# schematic.net
KiCad netlist of a schematic drawn in EasyEDA
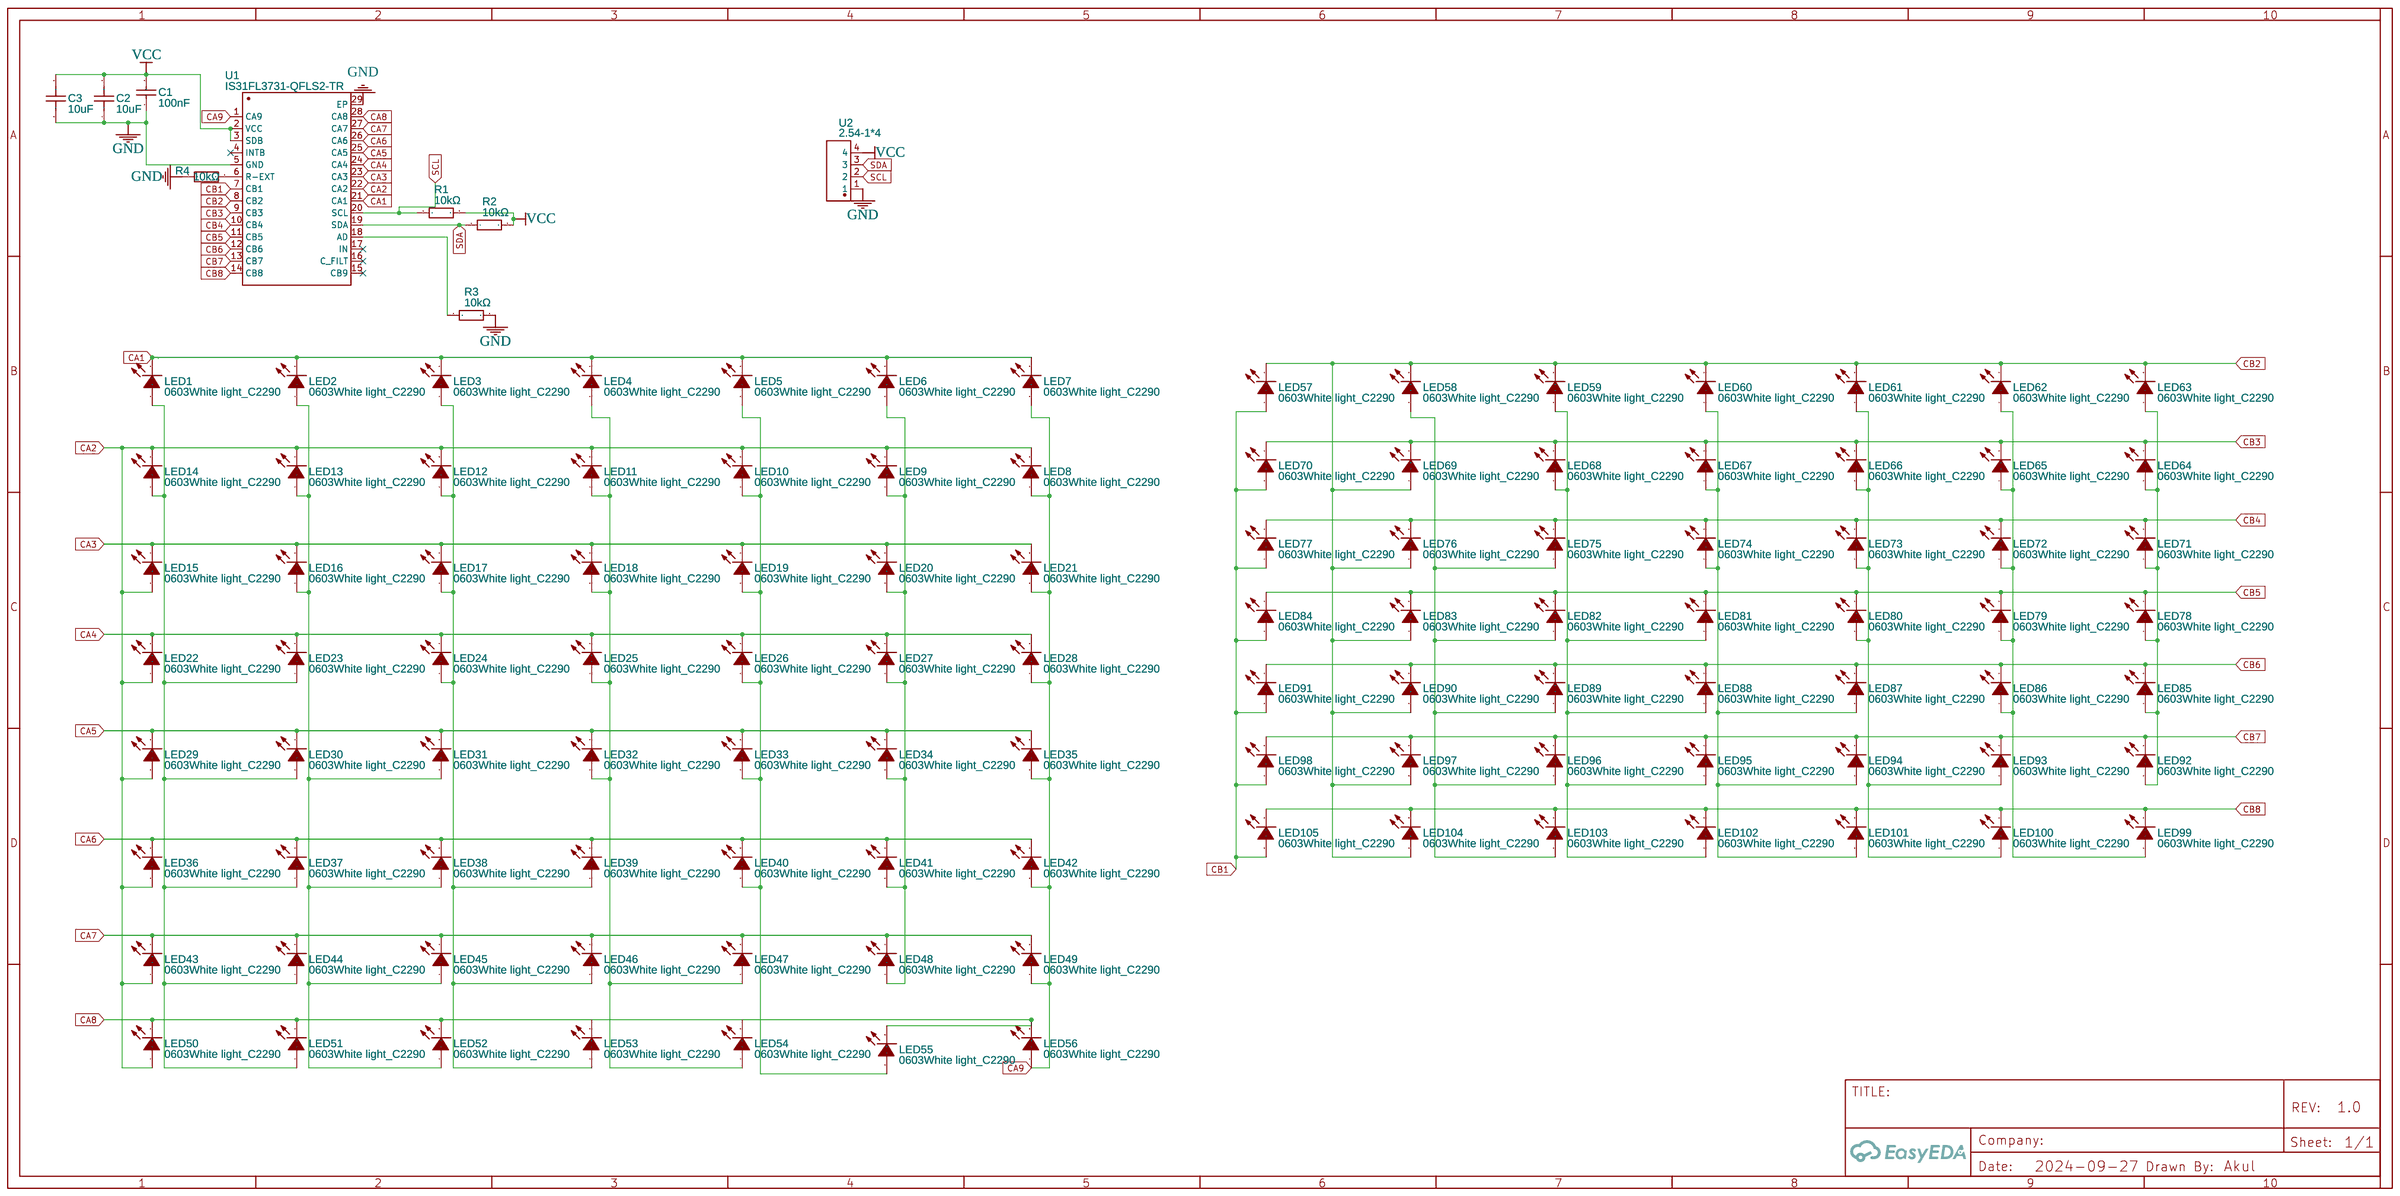
[diagram p0: schematic sheet]

(export (version "E")
  (design (tool "Eeschema 10.0.6"))
  (components
    (comp (ref "C1")
      (value "100nF")
      (fields
        (field (name "Manufacturer Part") "CL05B104KO5NNNC")
        (field (name "Manufacturer") "SAMSUNG(三星)")
      )
      (libsource (lib "") (part "CL05B104KO5NNNC"))
    )
    (comp (ref "C2")
      (value "10uF")
      (fields
        (field (name "Manufacturer Part") "CL10A106KP8NNNC")
        (field (name "Manufacturer") "SAMSUNG(三星)")
      )
      (libsource (lib "") (part "CL10A106KP8NNNC"))
    )
    (comp (ref "C3")
      (value "10uF")
      (fields
        (field (name "Manufacturer Part") "CL10A106KP8NNNC")
        (field (name "Manufacturer") "SAMSUNG(三星)")
      )
      (libsource (lib "") (part "CL10A106KP8NNNC"))
    )
    (comp (ref "LED1")
      (value "0603White light_C2290")
      (fields (field (name "Manufacturer Part") "KT-0603白灯") (field (name "Manufacturer") "KENTO"))
      (libsource (lib "") (part "0603White light_C2290"))
    )
    (comp (ref "LED2")
      (value "0603White light_C2290")
      (fields (field (name "Manufacturer Part") "KT-0603白灯") (field (name "Manufacturer") "KENTO"))
      (libsource (lib "") (part "0603White light_C2290"))
    )
    (comp (ref "LED3")
      (value "0603White light_C2290")
      (fields (field (name "Manufacturer Part") "KT-0603白灯") (field (name "Manufacturer") "KENTO"))
      (libsource (lib "") (part "0603White light_C2290"))
    )
    (comp (ref "LED4")
      (value "0603White light_C2290")
      (fields (field (name "Manufacturer Part") "KT-0603白灯") (field (name "Manufacturer") "KENTO"))
      (libsource (lib "") (part "0603White light_C2290"))
    )
    (comp (ref "LED5")
      (value "0603White light_C2290")
      (fields (field (name "Manufacturer Part") "KT-0603白灯") (field (name "Manufacturer") "KENTO"))
      (libsource (lib "") (part "0603White light_C2290"))
    )
    (comp (ref "LED6")
      (value "0603White light_C2290")
      (fields (field (name "Manufacturer Part") "KT-0603白灯") (field (name "Manufacturer") "KENTO"))
      (libsource (lib "") (part "0603White light_C2290"))
    )
    (comp (ref "LED7")
      (value "0603White light_C2290")
      (fields (field (name "Manufacturer Part") "KT-0603白灯") (field (name "Manufacturer") "KENTO"))
      (libsource (lib "") (part "0603White light_C2290"))
    )
    (comp (ref "LED8")
      (value "0603White light_C2290")
      (fields (field (name "Manufacturer Part") "KT-0603白灯") (field (name "Manufacturer") "KENTO"))
      (libsource (lib "") (part "0603White light_C2290"))
    )
    (comp (ref "LED9")
      (value "0603White light_C2290")
      (fields (field (name "Manufacturer Part") "KT-0603白灯") (field (name "Manufacturer") "KENTO"))
      (libsource (lib "") (part "0603White light_C2290"))
    )
    (comp (ref "LED10")
      (value "0603White light_C2290")
      (fields (field (name "Manufacturer Part") "KT-0603白灯") (field (name "Manufacturer") "KENTO"))
      (libsource (lib "") (part "0603White light_C2290"))
    )
    (comp (ref "LED11")
      (value "0603White light_C2290")
      (fields (field (name "Manufacturer Part") "KT-0603白灯") (field (name "Manufacturer") "KENTO"))
      (libsource (lib "") (part "0603White light_C2290"))
    )
    (comp (ref "LED12")
      (value "0603White light_C2290")
      (fields (field (name "Manufacturer Part") "KT-0603白灯") (field (name "Manufacturer") "KENTO"))
      (libsource (lib "") (part "0603White light_C2290"))
    )
    (comp (ref "LED13")
      (value "0603White light_C2290")
      (fields (field (name "Manufacturer Part") "KT-0603白灯") (field (name "Manufacturer") "KENTO"))
      (libsource (lib "") (part "0603White light_C2290"))
    )
    (comp (ref "LED14")
      (value "0603White light_C2290")
      (fields (field (name "Manufacturer Part") "KT-0603白灯") (field (name "Manufacturer") "KENTO"))
      (libsource (lib "") (part "0603White light_C2290"))
    )
    (comp (ref "LED15")
      (value "0603White light_C2290")
      (fields (field (name "Manufacturer Part") "KT-0603白灯") (field (name "Manufacturer") "KENTO"))
      (libsource (lib "") (part "0603White light_C2290"))
    )
    (comp (ref "LED16")
      (value "0603White light_C2290")
      (fields (field (name "Manufacturer Part") "KT-0603白灯") (field (name "Manufacturer") "KENTO"))
      (libsource (lib "") (part "0603White light_C2290"))
    )
    (comp (ref "LED17")
      (value "0603White light_C2290")
      (fields (field (name "Manufacturer Part") "KT-0603白灯") (field (name "Manufacturer") "KENTO"))
      (libsource (lib "") (part "0603White light_C2290"))
    )
    (comp (ref "LED18")
      (value "0603White light_C2290")
      (fields (field (name "Manufacturer Part") "KT-0603白灯") (field (name "Manufacturer") "KENTO"))
      (libsource (lib "") (part "0603White light_C2290"))
    )
    (comp (ref "LED19")
      (value "0603White light_C2290")
      (fields (field (name "Manufacturer Part") "KT-0603白灯") (field (name "Manufacturer") "KENTO"))
      (libsource (lib "") (part "0603White light_C2290"))
    )
    (comp (ref "LED20")
      (value "0603White light_C2290")
      (fields (field (name "Manufacturer Part") "KT-0603白灯") (field (name "Manufacturer") "KENTO"))
      (libsource (lib "") (part "0603White light_C2290"))
    )
    (comp (ref "LED21")
      (value "0603White light_C2290")
      (fields (field (name "Manufacturer Part") "KT-0603白灯") (field (name "Manufacturer") "KENTO"))
      (libsource (lib "") (part "0603White light_C2290"))
    )
    (comp (ref "LED22")
      (value "0603White light_C2290")
      (fields (field (name "Manufacturer Part") "KT-0603白灯") (field (name "Manufacturer") "KENTO"))
      (libsource (lib "") (part "0603White light_C2290"))
    )
    (comp (ref "LED23")
      (value "0603White light_C2290")
      (fields (field (name "Manufacturer Part") "KT-0603白灯") (field (name "Manufacturer") "KENTO"))
      (libsource (lib "") (part "0603White light_C2290"))
    )
    (comp (ref "LED24")
      (value "0603White light_C2290")
      (fields (field (name "Manufacturer Part") "KT-0603白灯") (field (name "Manufacturer") "KENTO"))
      (libsource (lib "") (part "0603White light_C2290"))
    )
    (comp (ref "LED25")
      (value "0603White light_C2290")
      (fields (field (name "Manufacturer Part") "KT-0603白灯") (field (name "Manufacturer") "KENTO"))
      (libsource (lib "") (part "0603White light_C2290"))
    )
    (comp (ref "LED26")
      (value "0603White light_C2290")
      (fields (field (name "Manufacturer Part") "KT-0603白灯") (field (name "Manufacturer") "KENTO"))
      (libsource (lib "") (part "0603White light_C2290"))
    )
    (comp (ref "LED27")
      (value "0603White light_C2290")
      (fields (field (name "Manufacturer Part") "KT-0603白灯") (field (name "Manufacturer") "KENTO"))
      (libsource (lib "") (part "0603White light_C2290"))
    )
    (comp (ref "LED28")
      (value "0603White light_C2290")
      (fields (field (name "Manufacturer Part") "KT-0603白灯") (field (name "Manufacturer") "KENTO"))
      (libsource (lib "") (part "0603White light_C2290"))
    )
    (comp (ref "LED29")
      (value "0603White light_C2290")
      (fields (field (name "Manufacturer Part") "KT-0603白灯") (field (name "Manufacturer") "KENTO"))
      (libsource (lib "") (part "0603White light_C2290"))
    )
    (comp (ref "LED30")
      (value "0603White light_C2290")
      (fields (field (name "Manufacturer Part") "KT-0603白灯") (field (name "Manufacturer") "KENTO"))
      (libsource (lib "") (part "0603White light_C2290"))
    )
    (comp (ref "LED31")
      (value "0603White light_C2290")
      (fields (field (name "Manufacturer Part") "KT-0603白灯") (field (name "Manufacturer") "KENTO"))
      (libsource (lib "") (part "0603White light_C2290"))
    )
    (comp (ref "LED32")
      (value "0603White light_C2290")
      (fields (field (name "Manufacturer Part") "KT-0603白灯") (field (name "Manufacturer") "KENTO"))
      (libsource (lib "") (part "0603White light_C2290"))
    )
    (comp (ref "LED33")
      (value "0603White light_C2290")
      (fields (field (name "Manufacturer Part") "KT-0603白灯") (field (name "Manufacturer") "KENTO"))
      (libsource (lib "") (part "0603White light_C2290"))
    )
    (comp (ref "LED34")
      (value "0603White light_C2290")
      (fields (field (name "Manufacturer Part") "KT-0603白灯") (field (name "Manufacturer") "KENTO"))
      (libsource (lib "") (part "0603White light_C2290"))
    )
    (comp (ref "LED35")
      (value "0603White light_C2290")
      (fields (field (name "Manufacturer Part") "KT-0603白灯") (field (name "Manufacturer") "KENTO"))
      (libsource (lib "") (part "0603White light_C2290"))
    )
    (comp (ref "LED36")
      (value "0603White light_C2290")
      (fields (field (name "Manufacturer Part") "KT-0603白灯") (field (name "Manufacturer") "KENTO"))
      (libsource (lib "") (part "0603White light_C2290"))
    )
    (comp (ref "LED37")
      (value "0603White light_C2290")
      (fields (field (name "Manufacturer Part") "KT-0603白灯") (field (name "Manufacturer") "KENTO"))
      (libsource (lib "") (part "0603White light_C2290"))
    )
    (comp (ref "LED38")
      (value "0603White light_C2290")
      (fields (field (name "Manufacturer Part") "KT-0603白灯") (field (name "Manufacturer") "KENTO"))
      (libsource (lib "") (part "0603White light_C2290"))
    )
    (comp (ref "LED39")
      (value "0603White light_C2290")
      (fields (field (name "Manufacturer Part") "KT-0603白灯") (field (name "Manufacturer") "KENTO"))
      (libsource (lib "") (part "0603White light_C2290"))
    )
    (comp (ref "LED40")
      (value "0603White light_C2290")
      (fields (field (name "Manufacturer Part") "KT-0603白灯") (field (name "Manufacturer") "KENTO"))
      (libsource (lib "") (part "0603White light_C2290"))
    )
    (comp (ref "LED41")
      (value "0603White light_C2290")
      (fields (field (name "Manufacturer Part") "KT-0603白灯") (field (name "Manufacturer") "KENTO"))
      (libsource (lib "") (part "0603White light_C2290"))
    )
    (comp (ref "LED42")
      (value "0603White light_C2290")
      (fields (field (name "Manufacturer Part") "KT-0603白灯") (field (name "Manufacturer") "KENTO"))
      (libsource (lib "") (part "0603White light_C2290"))
    )
    (comp (ref "LED43")
      (value "0603White light_C2290")
      (fields (field (name "Manufacturer Part") "KT-0603白灯") (field (name "Manufacturer") "KENTO"))
      (libsource (lib "") (part "0603White light_C2290"))
    )
    (comp (ref "LED44")
      (value "0603White light_C2290")
      (fields (field (name "Manufacturer Part") "KT-0603白灯") (field (name "Manufacturer") "KENTO"))
      (libsource (lib "") (part "0603White light_C2290"))
    )
    (comp (ref "LED45")
      (value "0603White light_C2290")
      (fields (field (name "Manufacturer Part") "KT-0603白灯") (field (name "Manufacturer") "KENTO"))
      (libsource (lib "") (part "0603White light_C2290"))
    )
    (comp (ref "LED46")
      (value "0603White light_C2290")
      (fields (field (name "Manufacturer Part") "KT-0603白灯") (field (name "Manufacturer") "KENTO"))
      (libsource (lib "") (part "0603White light_C2290"))
    )
    (comp (ref "LED47")
      (value "0603White light_C2290")
      (fields (field (name "Manufacturer Part") "KT-0603白灯") (field (name "Manufacturer") "KENTO"))
      (libsource (lib "") (part "0603White light_C2290"))
    )
    (comp (ref "LED48")
      (value "0603White light_C2290")
      (fields (field (name "Manufacturer Part") "KT-0603白灯") (field (name "Manufacturer") "KENTO"))
      (libsource (lib "") (part "0603White light_C2290"))
    )
    (comp (ref "LED49")
      (value "0603White light_C2290")
      (fields (field (name "Manufacturer Part") "KT-0603白灯") (field (name "Manufacturer") "KENTO"))
      (libsource (lib "") (part "0603White light_C2290"))
    )
    (comp (ref "LED50")
      (value "0603White light_C2290")
      (fields (field (name "Manufacturer Part") "KT-0603白灯") (field (name "Manufacturer") "KENTO"))
      (libsource (lib "") (part "0603White light_C2290"))
    )
    (comp (ref "LED51")
      (value "0603White light_C2290")
      (fields (field (name "Manufacturer Part") "KT-0603白灯") (field (name "Manufacturer") "KENTO"))
      (libsource (lib "") (part "0603White light_C2290"))
    )
    (comp (ref "LED52")
      (value "0603White light_C2290")
      (fields (field (name "Manufacturer Part") "KT-0603白灯") (field (name "Manufacturer") "KENTO"))
      (libsource (lib "") (part "0603White light_C2290"))
    )
    (comp (ref "LED53")
      (value "0603White light_C2290")
      (fields (field (name "Manufacturer Part") "KT-0603白灯") (field (name "Manufacturer") "KENTO"))
      (libsource (lib "") (part "0603White light_C2290"))
    )
    (comp (ref "LED54")
      (value "0603White light_C2290")
      (fields (field (name "Manufacturer Part") "KT-0603白灯") (field (name "Manufacturer") "KENTO"))
      (libsource (lib "") (part "0603White light_C2290"))
    )
    (comp (ref "LED55")
      (value "0603White light_C2290")
      (fields (field (name "Manufacturer Part") "KT-0603白灯") (field (name "Manufacturer") "KENTO"))
      (libsource (lib "") (part "0603White light_C2290"))
    )
    (comp (ref "LED56")
      (value "0603White light_C2290")
      (fields (field (name "Manufacturer Part") "KT-0603白灯") (field (name "Manufacturer") "KENTO"))
      (libsource (lib "") (part "0603White light_C2290"))
    )
    (comp (ref "LED57")
      (value "0603White light_C2290")
      (fields (field (name "Manufacturer Part") "KT-0603白灯") (field (name "Manufacturer") "KENTO"))
      (libsource (lib "") (part "0603White light_C2290_1"))
    )
    (comp (ref "LED58")
      (value "0603White light_C2290")
      (fields (field (name "Manufacturer Part") "KT-0603白灯") (field (name "Manufacturer") "KENTO"))
      (libsource (lib "") (part "0603White light_C2290_1"))
    )
    (comp (ref "LED59")
      (value "0603White light_C2290")
      (fields (field (name "Manufacturer Part") "KT-0603白灯") (field (name "Manufacturer") "KENTO"))
      (libsource (lib "") (part "0603White light_C2290_1"))
    )
    (comp (ref "LED60")
      (value "0603White light_C2290")
      (fields (field (name "Manufacturer Part") "KT-0603白灯") (field (name "Manufacturer") "KENTO"))
      (libsource (lib "") (part "0603White light_C2290_1"))
    )
    (comp (ref "LED61")
      (value "0603White light_C2290")
      (fields (field (name "Manufacturer Part") "KT-0603白灯") (field (name "Manufacturer") "KENTO"))
      (libsource (lib "") (part "0603White light_C2290_1"))
    )
    (comp (ref "LED62")
      (value "0603White light_C2290")
      (fields (field (name "Manufacturer Part") "KT-0603白灯") (field (name "Manufacturer") "KENTO"))
      (libsource (lib "") (part "0603White light_C2290_1"))
    )
    (comp (ref "LED63")
      (value "0603White light_C2290")
      (fields (field (name "Manufacturer Part") "KT-0603白灯") (field (name "Manufacturer") "KENTO"))
      (libsource (lib "") (part "0603White light_C2290_1"))
    )
    (comp (ref "LED64")
      (value "0603White light_C2290")
      (fields (field (name "Manufacturer Part") "KT-0603白灯") (field (name "Manufacturer") "KENTO"))
      (libsource (lib "") (part "0603White light_C2290_1"))
    )
    (comp (ref "LED65")
      (value "0603White light_C2290")
      (fields (field (name "Manufacturer Part") "KT-0603白灯") (field (name "Manufacturer") "KENTO"))
      (libsource (lib "") (part "0603White light_C2290_1"))
    )
    (comp (ref "LED66")
      (value "0603White light_C2290")
      (fields (field (name "Manufacturer Part") "KT-0603白灯") (field (name "Manufacturer") "KENTO"))
      (libsource (lib "") (part "0603White light_C2290_1"))
    )
    (comp (ref "LED67")
      (value "0603White light_C2290")
      (fields (field (name "Manufacturer Part") "KT-0603白灯") (field (name "Manufacturer") "KENTO"))
      (libsource (lib "") (part "0603White light_C2290_1"))
    )
    (comp (ref "LED68")
      (value "0603White light_C2290")
      (fields (field (name "Manufacturer Part") "KT-0603白灯") (field (name "Manufacturer") "KENTO"))
      (libsource (lib "") (part "0603White light_C2290_1"))
    )
    (comp (ref "LED69")
      (value "0603White light_C2290")
      (fields (field (name "Manufacturer Part") "KT-0603白灯") (field (name "Manufacturer") "KENTO"))
      (libsource (lib "") (part "0603White light_C2290_1"))
    )
    (comp (ref "LED70")
      (value "0603White light_C2290")
      (fields (field (name "Manufacturer Part") "KT-0603白灯") (field (name "Manufacturer") "KENTO"))
      (libsource (lib "") (part "0603White light_C2290_1"))
    )
    (comp (ref "LED71")
      (value "0603White light_C2290")
      (fields (field (name "Manufacturer Part") "KT-0603白灯") (field (name "Manufacturer") "KENTO"))
      (libsource (lib "") (part "0603White light_C2290_1"))
    )
    (comp (ref "LED72")
      (value "0603White light_C2290")
      (fields (field (name "Manufacturer Part") "KT-0603白灯") (field (name "Manufacturer") "KENTO"))
      (libsource (lib "") (part "0603White light_C2290_1"))
    )
    (comp (ref "LED73")
      (value "0603White light_C2290")
      (fields (field (name "Manufacturer Part") "KT-0603白灯") (field (name "Manufacturer") "KENTO"))
      (libsource (lib "") (part "0603White light_C2290_1"))
    )
    (comp (ref "LED74")
      (value "0603White light_C2290")
      (fields (field (name "Manufacturer Part") "KT-0603白灯") (field (name "Manufacturer") "KENTO"))
      (libsource (lib "") (part "0603White light_C2290_1"))
    )
    (comp (ref "LED75")
      (value "0603White light_C2290")
      (fields (field (name "Manufacturer Part") "KT-0603白灯") (field (name "Manufacturer") "KENTO"))
      (libsource (lib "") (part "0603White light_C2290_1"))
    )
    (comp (ref "LED76")
      (value "0603White light_C2290")
      (fields (field (name "Manufacturer Part") "KT-0603白灯") (field (name "Manufacturer") "KENTO"))
      (libsource (lib "") (part "0603White light_C2290_1"))
    )
    (comp (ref "LED77")
      (value "0603White light_C2290")
      (fields (field (name "Manufacturer Part") "KT-0603白灯") (field (name "Manufacturer") "KENTO"))
      (libsource (lib "") (part "0603White light_C2290_1"))
    )
    (comp (ref "LED78")
      (value "0603White light_C2290")
      (fields (field (name "Manufacturer Part") "KT-0603白灯") (field (name "Manufacturer") "KENTO"))
      (libsource (lib "") (part "0603White light_C2290_1"))
    )
    (comp (ref "LED79")
      (value "0603White light_C2290")
      (fields (field (name "Manufacturer Part") "KT-0603白灯") (field (name "Manufacturer") "KENTO"))
      (libsource (lib "") (part "0603White light_C2290_1"))
    )
    (comp (ref "LED80")
      (value "0603White light_C2290")
      (fields (field (name "Manufacturer Part") "KT-0603白灯") (field (name "Manufacturer") "KENTO"))
      (libsource (lib "") (part "0603White light_C2290_1"))
    )
    (comp (ref "LED81")
      (value "0603White light_C2290")
      (fields (field (name "Manufacturer Part") "KT-0603白灯") (field (name "Manufacturer") "KENTO"))
      (libsource (lib "") (part "0603White light_C2290_1"))
    )
    (comp (ref "LED82")
      (value "0603White light_C2290")
      (fields (field (name "Manufacturer Part") "KT-0603白灯") (field (name "Manufacturer") "KENTO"))
      (libsource (lib "") (part "0603White light_C2290_1"))
    )
    (comp (ref "LED83")
      (value "0603White light_C2290")
      (fields (field (name "Manufacturer Part") "KT-0603白灯") (field (name "Manufacturer") "KENTO"))
      (libsource (lib "") (part "0603White light_C2290_1"))
    )
    (comp (ref "LED84")
      (value "0603White light_C2290")
      (fields (field (name "Manufacturer Part") "KT-0603白灯") (field (name "Manufacturer") "KENTO"))
      (libsource (lib "") (part "0603White light_C2290_1"))
    )
    (comp (ref "LED85")
      (value "0603White light_C2290")
      (fields (field (name "Manufacturer Part") "KT-0603白灯") (field (name "Manufacturer") "KENTO"))
      (libsource (lib "") (part "0603White light_C2290_1"))
    )
    (comp (ref "LED86")
      (value "0603White light_C2290")
      (fields (field (name "Manufacturer Part") "KT-0603白灯") (field (name "Manufacturer") "KENTO"))
      (libsource (lib "") (part "0603White light_C2290_1"))
    )
    (comp (ref "LED87")
      (value "0603White light_C2290")
      (fields (field (name "Manufacturer Part") "KT-0603白灯") (field (name "Manufacturer") "KENTO"))
      (libsource (lib "") (part "0603White light_C2290_1"))
    )
    (comp (ref "LED88")
      (value "0603White light_C2290")
      (fields (field (name "Manufacturer Part") "KT-0603白灯") (field (name "Manufacturer") "KENTO"))
      (libsource (lib "") (part "0603White light_C2290_1"))
    )
    (comp (ref "LED89")
      (value "0603White light_C2290")
      (fields (field (name "Manufacturer Part") "KT-0603白灯") (field (name "Manufacturer") "KENTO"))
      (libsource (lib "") (part "0603White light_C2290_1"))
    )
    (comp (ref "LED90")
      (value "0603White light_C2290")
      (fields (field (name "Manufacturer Part") "KT-0603白灯") (field (name "Manufacturer") "KENTO"))
      (libsource (lib "") (part "0603White light_C2290_1"))
    )
    (comp (ref "LED91")
      (value "0603White light_C2290")
      (fields (field (name "Manufacturer Part") "KT-0603白灯") (field (name "Manufacturer") "KENTO"))
      (libsource (lib "") (part "0603White light_C2290_1"))
    )
    (comp (ref "LED92")
      (value "0603White light_C2290")
      (fields (field (name "Manufacturer Part") "KT-0603白灯") (field (name "Manufacturer") "KENTO"))
      (libsource (lib "") (part "0603White light_C2290_1"))
    )
    (comp (ref "LED93")
      (value "0603White light_C2290")
      (fields (field (name "Manufacturer Part") "KT-0603白灯") (field (name "Manufacturer") "KENTO"))
      (libsource (lib "") (part "0603White light_C2290_1"))
    )
    (comp (ref "LED94")
      (value "0603White light_C2290")
      (fields (field (name "Manufacturer Part") "KT-0603白灯") (field (name "Manufacturer") "KENTO"))
      (libsource (lib "") (part "0603White light_C2290_1"))
    )
    (comp (ref "LED95")
      (value "0603White light_C2290")
      (fields (field (name "Manufacturer Part") "KT-0603白灯") (field (name "Manufacturer") "KENTO"))
      (libsource (lib "") (part "0603White light_C2290_1"))
    )
    (comp (ref "LED96")
      (value "0603White light_C2290")
      (fields (field (name "Manufacturer Part") "KT-0603白灯") (field (name "Manufacturer") "KENTO"))
      (libsource (lib "") (part "0603White light_C2290_1"))
    )
    (comp (ref "LED97")
      (value "0603White light_C2290")
      (fields (field (name "Manufacturer Part") "KT-0603白灯") (field (name "Manufacturer") "KENTO"))
      (libsource (lib "") (part "0603White light_C2290_1"))
    )
    (comp (ref "LED98")
      (value "0603White light_C2290")
      (fields (field (name "Manufacturer Part") "KT-0603白灯") (field (name "Manufacturer") "KENTO"))
      (libsource (lib "") (part "0603White light_C2290_1"))
    )
    (comp (ref "LED99")
      (value "0603White light_C2290")
      (fields (field (name "Manufacturer Part") "KT-0603白灯") (field (name "Manufacturer") "KENTO"))
      (libsource (lib "") (part "0603White light_C2290_1"))
    )
    (comp (ref "LED100")
      (value "0603White light_C2290")
      (fields (field (name "Manufacturer Part") "KT-0603白灯") (field (name "Manufacturer") "KENTO"))
      (libsource (lib "") (part "0603White light_C2290_1"))
    )
    (comp (ref "LED101")
      (value "0603White light_C2290")
      (fields (field (name "Manufacturer Part") "KT-0603白灯") (field (name "Manufacturer") "KENTO"))
      (libsource (lib "") (part "0603White light_C2290_1"))
    )
    (comp (ref "LED102")
      (value "0603White light_C2290")
      (fields (field (name "Manufacturer Part") "KT-0603白灯") (field (name "Manufacturer") "KENTO"))
      (libsource (lib "") (part "0603White light_C2290_1"))
    )
    (comp (ref "LED103")
      (value "0603White light_C2290")
      (fields (field (name "Manufacturer Part") "KT-0603白灯") (field (name "Manufacturer") "KENTO"))
      (libsource (lib "") (part "0603White light_C2290_1"))
    )
    (comp (ref "LED104")
      (value "0603White light_C2290")
      (fields (field (name "Manufacturer Part") "KT-0603白灯") (field (name "Manufacturer") "KENTO"))
      (libsource (lib "") (part "0603White light_C2290_1"))
    )
    (comp (ref "LED105")
      (value "0603White light_C2290")
      (fields (field (name "Manufacturer Part") "KT-0603白灯") (field (name "Manufacturer") "KENTO"))
      (libsource (lib "") (part "0603White light_C2290_1"))
    )
    (comp (ref "R1")
      (value "10kΩ")
      (fields
        (field (name "Manufacturer Part") "0402WGF1002TCE")
        (field (name "Manufacturer") "UNI-ROYAL(厚声)")
      )
      (libsource (lib "") (part "0402WGF1002TCE"))
    )
    (comp (ref "R2")
      (value "10kΩ")
      (fields
        (field (name "Manufacturer Part") "0402WGF1002TCE")
        (field (name "Manufacturer") "UNI-ROYAL(厚声)")
      )
      (libsource (lib "") (part "0402WGF1002TCE"))
    )
    (comp (ref "R3")
      (value "10kΩ")
      (fields
        (field (name "Manufacturer Part") "0402WGF1002TCE")
        (field (name "Manufacturer") "UNI-ROYAL(厚声)")
      )
      (libsource (lib "") (part "0402WGF1002TCE"))
    )
    (comp (ref "R4")
      (value "10kΩ")
      (fields
        (field (name "Manufacturer Part") "0402WGF1002TCE")
        (field (name "Manufacturer") "UNI-ROYAL(厚声)")
      )
      (libsource (lib "") (part "0402WGF1002TCE"))
    )
    (comp (ref "U1")
      (value "IS31FL3731-QFLS2-TR")
      (fields (field (name "Manufacturer") "ISSI(美国芯成)"))
      (libsource (lib "") (part "IS31FL3731-QFLS2-TR"))
    )
    (comp (ref "U2")
      (value "2.54-1*4")
      (fields (field (name "Manufacturer") "ZHOURI(洲日)"))
      (libsource (lib "") (part "2.54-1*4"))
    )
  )
  (nets
    (net (code "1") (name "CA1") (class "Default")
      (node (ref "LED1") (pin "2") (pinfunction "K_2") (pintype "unspecified"))
      (node (ref "LED2") (pin "2") (pinfunction "K_2") (pintype "unspecified"))
      (node (ref "LED3") (pin "2") (pinfunction "K_2") (pintype "unspecified"))
      (node (ref "LED4") (pin "2") (pinfunction "K_2") (pintype "unspecified"))
      (node (ref "LED5") (pin "2") (pinfunction "K_2") (pintype "unspecified"))
      (node (ref "LED6") (pin "2") (pinfunction "K_2") (pintype "unspecified"))
      (node (ref "LED7") (pin "2") (pinfunction "K_2") (pintype "unspecified"))
      (node (ref "U1") (pin "21") (pinfunction "CA1_21") (pintype "unspecified"))
    )
    (net (code "2") (name "CA2") (class "Default")
      (node (ref "LED10") (pin "2") (pinfunction "K_2") (pintype "unspecified"))
      (node (ref "LED11") (pin "2") (pinfunction "K_2") (pintype "unspecified"))
      (node (ref "LED12") (pin "2") (pinfunction "K_2") (pintype "unspecified"))
      (node (ref "LED13") (pin "2") (pinfunction "K_2") (pintype "unspecified"))
      (node (ref "LED14") (pin "2") (pinfunction "K_2") (pintype "unspecified"))
      (node (ref "LED15") (pin "1") (pinfunction "A_1") (pintype "unspecified"))
      (node (ref "LED22") (pin "1") (pinfunction "A_1") (pintype "unspecified"))
      (node (ref "LED29") (pin "1") (pinfunction "A_1") (pintype "unspecified"))
      (node (ref "LED36") (pin "1") (pinfunction "A_1") (pintype "unspecified"))
      (node (ref "LED43") (pin "1") (pinfunction "A_1") (pintype "unspecified"))
      (node (ref "LED50") (pin "1") (pinfunction "A_1") (pintype "unspecified"))
      (node (ref "LED8") (pin "2") (pinfunction "K_2") (pintype "unspecified"))
      (node (ref "LED9") (pin "2") (pinfunction "K_2") (pintype "unspecified"))
      (node (ref "U1") (pin "22") (pinfunction "CA2_22") (pintype "unspecified"))
    )
    (net (code "3") (name "CA3") (class "Default")
      (node (ref "LED15") (pin "2") (pinfunction "K_2") (pintype "unspecified"))
      (node (ref "LED16") (pin "2") (pinfunction "K_2") (pintype "unspecified"))
      (node (ref "LED17") (pin "2") (pinfunction "K_2") (pintype "unspecified"))
      (node (ref "LED18") (pin "2") (pinfunction "K_2") (pintype "unspecified"))
      (node (ref "LED19") (pin "2") (pinfunction "K_2") (pintype "unspecified"))
      (node (ref "LED20") (pin "2") (pinfunction "K_2") (pintype "unspecified"))
      (node (ref "LED21") (pin "2") (pinfunction "K_2") (pintype "unspecified"))
      (node (ref "U1") (pin "23") (pinfunction "CA3_23") (pintype "unspecified"))
    )
    (net (code "4") (name "CA4") (class "Default")
      (node (ref "LED22") (pin "2") (pinfunction "K_2") (pintype "unspecified"))
      (node (ref "LED23") (pin "2") (pinfunction "K_2") (pintype "unspecified"))
      (node (ref "LED24") (pin "2") (pinfunction "K_2") (pintype "unspecified"))
      (node (ref "LED25") (pin "2") (pinfunction "K_2") (pintype "unspecified"))
      (node (ref "LED26") (pin "2") (pinfunction "K_2") (pintype "unspecified"))
      (node (ref "LED27") (pin "2") (pinfunction "K_2") (pintype "unspecified"))
      (node (ref "LED28") (pin "2") (pinfunction "K_2") (pintype "unspecified"))
      (node (ref "U1") (pin "24") (pinfunction "CA4_24") (pintype "unspecified"))
    )
    (net (code "5") (name "CA5") (class "Default")
      (node (ref "LED29") (pin "2") (pinfunction "K_2") (pintype "unspecified"))
      (node (ref "LED30") (pin "2") (pinfunction "K_2") (pintype "unspecified"))
      (node (ref "LED31") (pin "2") (pinfunction "K_2") (pintype "unspecified"))
      (node (ref "LED32") (pin "2") (pinfunction "K_2") (pintype "unspecified"))
      (node (ref "LED33") (pin "2") (pinfunction "K_2") (pintype "unspecified"))
      (node (ref "LED34") (pin "2") (pinfunction "K_2") (pintype "unspecified"))
      (node (ref "LED35") (pin "2") (pinfunction "K_2") (pintype "unspecified"))
      (node (ref "U1") (pin "25") (pinfunction "CA5_25") (pintype "unspecified"))
    )
    (net (code "6") (name "CA6") (class "Default")
      (node (ref "LED36") (pin "2") (pinfunction "K_2") (pintype "unspecified"))
      (node (ref "LED37") (pin "2") (pinfunction "K_2") (pintype "unspecified"))
      (node (ref "LED38") (pin "2") (pinfunction "K_2") (pintype "unspecified"))
      (node (ref "LED39") (pin "2") (pinfunction "K_2") (pintype "unspecified"))
      (node (ref "LED40") (pin "2") (pinfunction "K_2") (pintype "unspecified"))
      (node (ref "LED41") (pin "2") (pinfunction "K_2") (pintype "unspecified"))
      (node (ref "LED42") (pin "2") (pinfunction "K_2") (pintype "unspecified"))
      (node (ref "U1") (pin "26") (pinfunction "CA6_26") (pintype "unspecified"))
    )
    (net (code "7") (name "CA7") (class "Default")
      (node (ref "LED43") (pin "2") (pinfunction "K_2") (pintype "unspecified"))
      (node (ref "LED44") (pin "2") (pinfunction "K_2") (pintype "unspecified"))
      (node (ref "LED45") (pin "2") (pinfunction "K_2") (pintype "unspecified"))
      (node (ref "LED46") (pin "2") (pinfunction "K_2") (pintype "unspecified"))
      (node (ref "LED47") (pin "2") (pinfunction "K_2") (pintype "unspecified"))
      (node (ref "LED48") (pin "2") (pinfunction "K_2") (pintype "unspecified"))
      (node (ref "LED49") (pin "2") (pinfunction "K_2") (pintype "unspecified"))
      (node (ref "U1") (pin "27") (pinfunction "CA7_27") (pintype "unspecified"))
    )
    (net (code "8") (name "CA8") (class "Default")
      (node (ref "LED50") (pin "2") (pinfunction "K_2") (pintype "unspecified"))
      (node (ref "LED51") (pin "2") (pinfunction "K_2") (pintype "unspecified"))
      (node (ref "LED52") (pin "2") (pinfunction "K_2") (pintype "unspecified"))
      (node (ref "LED53") (pin "2") (pinfunction "K_2") (pintype "unspecified"))
      (node (ref "LED54") (pin "2") (pinfunction "K_2") (pintype "unspecified"))
      (node (ref "LED55") (pin "2") (pinfunction "K_2") (pintype "unspecified"))
      (node (ref "LED56") (pin "2") (pinfunction "K_2") (pintype "unspecified"))
      (node (ref "U1") (pin "28") (pinfunction "CA8_28") (pintype "unspecified"))
    )
    (net (code "9") (name "CA9") (class "Default")
      (node (ref "LED21") (pin "1") (pinfunction "A_1") (pintype "unspecified"))
      (node (ref "LED28") (pin "1") (pinfunction "A_1") (pintype "unspecified"))
      (node (ref "LED35") (pin "1") (pinfunction "A_1") (pintype "unspecified"))
      (node (ref "LED42") (pin "1") (pinfunction "A_1") (pintype "unspecified"))
      (node (ref "LED49") (pin "1") (pinfunction "A_1") (pintype "unspecified"))
      (node (ref "LED56") (pin "1") (pinfunction "A_1") (pintype "unspecified"))
      (node (ref "LED7") (pin "1") (pinfunction "A_1") (pintype "unspecified"))
      (node (ref "LED8") (pin "1") (pinfunction "A_1") (pintype "unspecified"))
      (node (ref "U1") (pin "1") (pinfunction "CA9_1") (pintype "unspecified"))
    )
    (net (code "10") (name "CB1") (class "Default")
      (node (ref "LED105") (pin "1") (pinfunction "A_1") (pintype "unspecified"))
      (node (ref "LED57") (pin "1") (pinfunction "A_1") (pintype "unspecified"))
      (node (ref "LED70") (pin "1") (pinfunction "A_1") (pintype "unspecified"))
      (node (ref "LED77") (pin "1") (pinfunction "A_1") (pintype "unspecified"))
      (node (ref "LED84") (pin "1") (pinfunction "A_1") (pintype "unspecified"))
      (node (ref "LED91") (pin "1") (pinfunction "A_1") (pintype "unspecified"))
      (node (ref "LED98") (pin "1") (pinfunction "A_1") (pintype "unspecified"))
      (node (ref "U1") (pin "7") (pinfunction "CB1_7") (pintype "unspecified"))
    )
    (net (code "11") (name "CB2") (class "Default")
      (node (ref "LED104") (pin "1") (pinfunction "A_1") (pintype "unspecified"))
      (node (ref "LED57") (pin "2") (pinfunction "K_2") (pintype "unspecified"))
      (node (ref "LED58") (pin "2") (pinfunction "K_2") (pintype "unspecified"))
      (node (ref "LED59") (pin "2") (pinfunction "K_2") (pintype "unspecified"))
      (node (ref "LED60") (pin "2") (pinfunction "K_2") (pintype "unspecified"))
      (node (ref "LED61") (pin "2") (pinfunction "K_2") (pintype "unspecified"))
      (node (ref "LED62") (pin "2") (pinfunction "K_2") (pintype "unspecified"))
      (node (ref "LED63") (pin "2") (pinfunction "K_2") (pintype "unspecified"))
      (node (ref "LED69") (pin "1") (pinfunction "A_1") (pintype "unspecified"))
      (node (ref "LED76") (pin "1") (pinfunction "A_1") (pintype "unspecified"))
      (node (ref "LED83") (pin "1") (pinfunction "A_1") (pintype "unspecified"))
      (node (ref "LED90") (pin "1") (pinfunction "A_1") (pintype "unspecified"))
      (node (ref "LED97") (pin "1") (pinfunction "A_1") (pintype "unspecified"))
      (node (ref "U1") (pin "8") (pinfunction "CB2_8") (pintype "unspecified"))
    )
    (net (code "12") (name "CB3") (class "Default")
      (node (ref "LED64") (pin "2") (pinfunction "K_2") (pintype "unspecified"))
      (node (ref "LED65") (pin "2") (pinfunction "K_2") (pintype "unspecified"))
      (node (ref "LED66") (pin "2") (pinfunction "K_2") (pintype "unspecified"))
      (node (ref "LED67") (pin "2") (pinfunction "K_2") (pintype "unspecified"))
      (node (ref "LED68") (pin "2") (pinfunction "K_2") (pintype "unspecified"))
      (node (ref "LED69") (pin "2") (pinfunction "K_2") (pintype "unspecified"))
      (node (ref "LED70") (pin "2") (pinfunction "K_2") (pintype "unspecified"))
      (node (ref "U1") (pin "9") (pinfunction "CB3_9") (pintype "unspecified"))
    )
    (net (code "13") (name "CB4") (class "Default")
      (node (ref "LED71") (pin "2") (pinfunction "K_2") (pintype "unspecified"))
      (node (ref "LED72") (pin "2") (pinfunction "K_2") (pintype "unspecified"))
      (node (ref "LED73") (pin "2") (pinfunction "K_2") (pintype "unspecified"))
      (node (ref "LED74") (pin "2") (pinfunction "K_2") (pintype "unspecified"))
      (node (ref "LED75") (pin "2") (pinfunction "K_2") (pintype "unspecified"))
      (node (ref "LED76") (pin "2") (pinfunction "K_2") (pintype "unspecified"))
      (node (ref "LED77") (pin "2") (pinfunction "K_2") (pintype "unspecified"))
      (node (ref "U1") (pin "10") (pinfunction "CB4_10") (pintype "unspecified"))
    )
    (net (code "14") (name "CB5") (class "Default")
      (node (ref "LED78") (pin "2") (pinfunction "K_2") (pintype "unspecified"))
      (node (ref "LED79") (pin "2") (pinfunction "K_2") (pintype "unspecified"))
      (node (ref "LED80") (pin "2") (pinfunction "K_2") (pintype "unspecified"))
      (node (ref "LED81") (pin "2") (pinfunction "K_2") (pintype "unspecified"))
      (node (ref "LED82") (pin "2") (pinfunction "K_2") (pintype "unspecified"))
      (node (ref "LED83") (pin "2") (pinfunction "K_2") (pintype "unspecified"))
      (node (ref "LED84") (pin "2") (pinfunction "K_2") (pintype "unspecified"))
      (node (ref "U1") (pin "11") (pinfunction "CB5_11") (pintype "unspecified"))
    )
    (net (code "15") (name "CB6") (class "Default")
      (node (ref "LED85") (pin "2") (pinfunction "K_2") (pintype "unspecified"))
      (node (ref "LED86") (pin "2") (pinfunction "K_2") (pintype "unspecified"))
      (node (ref "LED87") (pin "2") (pinfunction "K_2") (pintype "unspecified"))
      (node (ref "LED88") (pin "2") (pinfunction "K_2") (pintype "unspecified"))
      (node (ref "LED89") (pin "2") (pinfunction "K_2") (pintype "unspecified"))
      (node (ref "LED90") (pin "2") (pinfunction "K_2") (pintype "unspecified"))
      (node (ref "LED91") (pin "2") (pinfunction "K_2") (pintype "unspecified"))
      (node (ref "U1") (pin "12") (pinfunction "CB6_12") (pintype "unspecified"))
    )
    (net (code "16") (name "CB7") (class "Default")
      (node (ref "LED92") (pin "2") (pinfunction "K_2") (pintype "unspecified"))
      (node (ref "LED93") (pin "2") (pinfunction "K_2") (pintype "unspecified"))
      (node (ref "LED94") (pin "2") (pinfunction "K_2") (pintype "unspecified"))
      (node (ref "LED95") (pin "2") (pinfunction "K_2") (pintype "unspecified"))
      (node (ref "LED96") (pin "2") (pinfunction "K_2") (pintype "unspecified"))
      (node (ref "LED97") (pin "2") (pinfunction "K_2") (pintype "unspecified"))
      (node (ref "LED98") (pin "2") (pinfunction "K_2") (pintype "unspecified"))
      (node (ref "U1") (pin "13") (pinfunction "CB7_13") (pintype "unspecified"))
    )
    (net (code "17") (name "CB8") (class "Default")
      (node (ref "LED100") (pin "2") (pinfunction "K_2") (pintype "unspecified"))
      (node (ref "LED101") (pin "2") (pinfunction "K_2") (pintype "unspecified"))
      (node (ref "LED102") (pin "2") (pinfunction "K_2") (pintype "unspecified"))
      (node (ref "LED103") (pin "2") (pinfunction "K_2") (pintype "unspecified"))
      (node (ref "LED104") (pin "2") (pinfunction "K_2") (pintype "unspecified"))
      (node (ref "LED105") (pin "2") (pinfunction "K_2") (pintype "unspecified"))
      (node (ref "LED99") (pin "2") (pinfunction "K_2") (pintype "unspecified"))
      (node (ref "U1") (pin "14") (pinfunction "CB8_14") (pintype "unspecified"))
    )
    (net (code "18") (name "GND") (class "Default")
      (node (ref "C1") (pin "1") (pinfunction "1_1") (pintype "input"))
      (node (ref "C2") (pin "1") (pinfunction "1_1") (pintype "unspecified"))
      (node (ref "C3") (pin "1") (pinfunction "1_1") (pintype "unspecified"))
      (node (ref "R3") (pin "2") (pinfunction "2_2") (pintype "input"))
      (node (ref "R4") (pin "1") (pinfunction "1_1") (pintype "input"))
      (node (ref "U1") (pin "29") (pinfunction "EP_29") (pintype "unspecified"))
      (node (ref "U1") (pin "5") (pinfunction "GND_5") (pintype "unspecified"))
      (node (ref "U2") (pin "1") (pinfunction "1_1") (pintype "unspecified"))
    )
    (net (code "19") (name "Net-(LED1-A)") (class "Default")
      (node (ref "LED1") (pin "1") (pinfunction "A_1") (pintype "unspecified"))
      (node (ref "LED14") (pin "1") (pinfunction "A_1") (pintype "unspecified"))
      (node (ref "LED23") (pin "1") (pinfunction "A_1") (pintype "unspecified"))
      (node (ref "LED30") (pin "1") (pinfunction "A_1") (pintype "unspecified"))
      (node (ref "LED37") (pin "1") (pinfunction "A_1") (pintype "unspecified"))
      (node (ref "LED44") (pin "1") (pinfunction "A_1") (pintype "unspecified"))
      (node (ref "LED51") (pin "1") (pinfunction "A_1") (pintype "unspecified"))
    )
    (net (code "20") (name "Net-(LED10-A)") (class "Default")
      (node (ref "LED10") (pin "1") (pinfunction "A_1") (pintype "unspecified"))
      (node (ref "LED19") (pin "1") (pinfunction "A_1") (pintype "unspecified"))
      (node (ref "LED26") (pin "1") (pinfunction "A_1") (pintype "unspecified"))
      (node (ref "LED33") (pin "1") (pinfunction "A_1") (pintype "unspecified"))
      (node (ref "LED40") (pin "1") (pinfunction "A_1") (pintype "unspecified"))
      (node (ref "LED5") (pin "1") (pinfunction "A_1") (pintype "unspecified"))
      (node (ref "LED55") (pin "1") (pinfunction "A_1") (pintype "unspecified"))
    )
    (net (code "21") (name "Net-(LED11-A)") (class "Default")
      (node (ref "LED11") (pin "1") (pinfunction "A_1") (pintype "unspecified"))
      (node (ref "LED18") (pin "1") (pinfunction "A_1") (pintype "unspecified"))
      (node (ref "LED25") (pin "1") (pinfunction "A_1") (pintype "unspecified"))
      (node (ref "LED32") (pin "1") (pinfunction "A_1") (pintype "unspecified"))
      (node (ref "LED4") (pin "1") (pinfunction "A_1") (pintype "unspecified"))
      (node (ref "LED47") (pin "1") (pinfunction "A_1") (pintype "unspecified"))
      (node (ref "LED54") (pin "1") (pinfunction "A_1") (pintype "unspecified"))
    )
    (net (code "22") (name "Net-(LED12-A)") (class "Default")
      (node (ref "LED12") (pin "1") (pinfunction "A_1") (pintype "unspecified"))
      (node (ref "LED17") (pin "1") (pinfunction "A_1") (pintype "unspecified"))
      (node (ref "LED24") (pin "1") (pinfunction "A_1") (pintype "unspecified"))
      (node (ref "LED3") (pin "1") (pinfunction "A_1") (pintype "unspecified"))
      (node (ref "LED39") (pin "1") (pinfunction "A_1") (pintype "unspecified"))
      (node (ref "LED46") (pin "1") (pinfunction "A_1") (pintype "unspecified"))
      (node (ref "LED53") (pin "1") (pinfunction "A_1") (pintype "unspecified"))
    )
    (net (code "23") (name "Net-(LED13-A)") (class "Default")
      (node (ref "LED13") (pin "1") (pinfunction "A_1") (pintype "unspecified"))
      (node (ref "LED16") (pin "1") (pinfunction "A_1") (pintype "unspecified"))
      (node (ref "LED2") (pin "1") (pinfunction "A_1") (pintype "unspecified"))
      (node (ref "LED31") (pin "1") (pinfunction "A_1") (pintype "unspecified"))
      (node (ref "LED38") (pin "1") (pinfunction "A_1") (pintype "unspecified"))
      (node (ref "LED45") (pin "1") (pinfunction "A_1") (pintype "unspecified"))
      (node (ref "LED52") (pin "1") (pinfunction "A_1") (pintype "unspecified"))
    )
    (net (code "24") (name "Net-(LED20-A)") (class "Default")
      (node (ref "LED20") (pin "1") (pinfunction "A_1") (pintype "unspecified"))
      (node (ref "LED27") (pin "1") (pinfunction "A_1") (pintype "unspecified"))
      (node (ref "LED34") (pin "1") (pinfunction "A_1") (pintype "unspecified"))
      (node (ref "LED41") (pin "1") (pinfunction "A_1") (pintype "unspecified"))
      (node (ref "LED48") (pin "1") (pinfunction "A_1") (pintype "unspecified"))
      (node (ref "LED6") (pin "1") (pinfunction "A_1") (pintype "unspecified"))
      (node (ref "LED9") (pin "1") (pinfunction "A_1") (pintype "unspecified"))
    )
    (net (code "25") (name "Net-(LED62-A)") (class "Default")
      (node (ref "LED62") (pin "1") (pinfunction "A_1") (pintype "unspecified"))
      (node (ref "LED65") (pin "1") (pinfunction "A_1") (pintype "unspecified"))
      (node (ref "LED72") (pin "1") (pinfunction "A_1") (pintype "unspecified"))
      (node (ref "LED79") (pin "1") (pinfunction "A_1") (pintype "unspecified"))
      (node (ref "LED86") (pin "1") (pinfunction "A_1") (pintype "unspecified"))
      (node (ref "LED99") (pin "1") (pinfunction "A_1") (pintype "unspecified"))
    )
    (net (code "26") (name "Net-(LED63-A)") (class "Default")
      (node (ref "LED63") (pin "1") (pinfunction "A_1") (pintype "unspecified"))
      (node (ref "LED64") (pin "1") (pinfunction "A_1") (pintype "unspecified"))
      (node (ref "LED71") (pin "1") (pinfunction "A_1") (pintype "unspecified"))
      (node (ref "LED78") (pin "1") (pinfunction "A_1") (pintype "unspecified"))
      (node (ref "LED85") (pin "1") (pinfunction "A_1") (pintype "unspecified"))
      (node (ref "LED92") (pin "1") (pinfunction "A_1") (pintype "unspecified"))
    )
    (net (code "27") (name "Net-(LED100-A)") (class "Default")
      (node (ref "LED100") (pin "1") (pinfunction "A_1") (pintype "unspecified"))
      (node (ref "LED61") (pin "1") (pinfunction "A_1") (pintype "unspecified"))
      (node (ref "LED66") (pin "1") (pinfunction "A_1") (pintype "unspecified"))
      (node (ref "LED73") (pin "1") (pinfunction "A_1") (pintype "unspecified"))
      (node (ref "LED80") (pin "1") (pinfunction "A_1") (pintype "unspecified"))
      (node (ref "LED93") (pin "1") (pinfunction "A_1") (pintype "unspecified"))
    )
    (net (code "28") (name "Net-(LED101-A)") (class "Default")
      (node (ref "LED101") (pin "1") (pinfunction "A_1") (pintype "unspecified"))
      (node (ref "LED60") (pin "1") (pinfunction "A_1") (pintype "unspecified"))
      (node (ref "LED67") (pin "1") (pinfunction "A_1") (pintype "unspecified"))
      (node (ref "LED74") (pin "1") (pinfunction "A_1") (pintype "unspecified"))
      (node (ref "LED87") (pin "1") (pinfunction "A_1") (pintype "unspecified"))
      (node (ref "LED94") (pin "1") (pinfunction "A_1") (pintype "unspecified"))
    )
    (net (code "29") (name "Net-(LED102-A)") (class "Default")
      (node (ref "LED102") (pin "1") (pinfunction "A_1") (pintype "unspecified"))
      (node (ref "LED59") (pin "1") (pinfunction "A_1") (pintype "unspecified"))
      (node (ref "LED68") (pin "1") (pinfunction "A_1") (pintype "unspecified"))
      (node (ref "LED81") (pin "1") (pinfunction "A_1") (pintype "unspecified"))
      (node (ref "LED88") (pin "1") (pinfunction "A_1") (pintype "unspecified"))
      (node (ref "LED95") (pin "1") (pinfunction "A_1") (pintype "unspecified"))
    )
    (net (code "30") (name "Net-(LED103-A)") (class "Default")
      (node (ref "LED103") (pin "1") (pinfunction "A_1") (pintype "unspecified"))
      (node (ref "LED58") (pin "1") (pinfunction "A_1") (pintype "unspecified"))
      (node (ref "LED75") (pin "1") (pinfunction "A_1") (pintype "unspecified"))
      (node (ref "LED82") (pin "1") (pinfunction "A_1") (pintype "unspecified"))
      (node (ref "LED89") (pin "1") (pinfunction "A_1") (pintype "unspecified"))
      (node (ref "LED96") (pin "1") (pinfunction "A_1") (pintype "unspecified"))
    )
    (net (code "31") (name "Net-(U1-AD)") (class "Default")
      (node (ref "R3") (pin "1") (pinfunction "1_1") (pintype "input"))
      (node (ref "U1") (pin "18") (pinfunction "AD_18") (pintype "unspecified"))
    )
    (net (code "32") (name "Net-(U1-R-EXT)") (class "Default")
      (node (ref "R4") (pin "2") (pinfunction "2_2") (pintype "input"))
      (node (ref "U1") (pin "6") (pinfunction "R-EXT_6") (pintype "unspecified"))
    )
    (net (code "33") (name "SCL") (class "Default")
      (node (ref "R1") (pin "1") (pinfunction "1_1") (pintype "input"))
      (node (ref "U1") (pin "20") (pinfunction "SCL_20") (pintype "unspecified"))
      (node (ref "U2") (pin "2") (pinfunction "2_2") (pintype "unspecified"))
    )
    (net (code "34") (name "SDA") (class "Default")
      (node (ref "R2") (pin "1") (pinfunction "1_1") (pintype "input"))
      (node (ref "U1") (pin "19") (pinfunction "SDA_19") (pintype "unspecified"))
      (node (ref "U2") (pin "3") (pinfunction "3_3") (pintype "unspecified"))
    )
    (net (code "35") (name "VCC") (class "Default")
      (node (ref "C1") (pin "2") (pinfunction "2_2") (pintype "input"))
      (node (ref "C2") (pin "2") (pinfunction "2_2") (pintype "unspecified"))
      (node (ref "C3") (pin "2") (pinfunction "2_2") (pintype "unspecified"))
      (node (ref "R1") (pin "2") (pinfunction "2_2") (pintype "input"))
      (node (ref "R2") (pin "2") (pinfunction "2_2") (pintype "input"))
      (node (ref "U1") (pin "2") (pinfunction "VCC_2") (pintype "unspecified"))
      (node (ref "U1") (pin "3") (pinfunction "SDB_3") (pintype "unspecified"))
      (node (ref "U2") (pin "4") (pinfunction "4_4") (pintype "unspecified"))
    )
    (net (code "36") (name "unconnected-(U1-CB9-Pad15)") (class "Default")
      (node (ref "U1") (pin "15") (pinfunction "CB9_15") (pintype "unspecified+no_connect"))
    )
    (net (code "37") (name "unconnected-(U1-C_FILT-Pad16)") (class "Default")
      (node (ref "U1") (pin "16") (pinfunction "C_FILT_16") (pintype "unspecified+no_connect"))
    )
    (net (code "38") (name "unconnected-(U1-IN-Pad17)") (class "Default")
      (node (ref "U1") (pin "17") (pinfunction "IN_17") (pintype "unspecified+no_connect"))
    )
    (net (code "39") (name "unconnected-(U1-INTB-Pad4)") (class "Default")
      (node (ref "U1") (pin "4") (pinfunction "INTB_4") (pintype "unspecified+no_connect"))
    )
  )
)
